# JTAG_MCU.net
KiCad netlist of a schematic drawn in Altium Designer
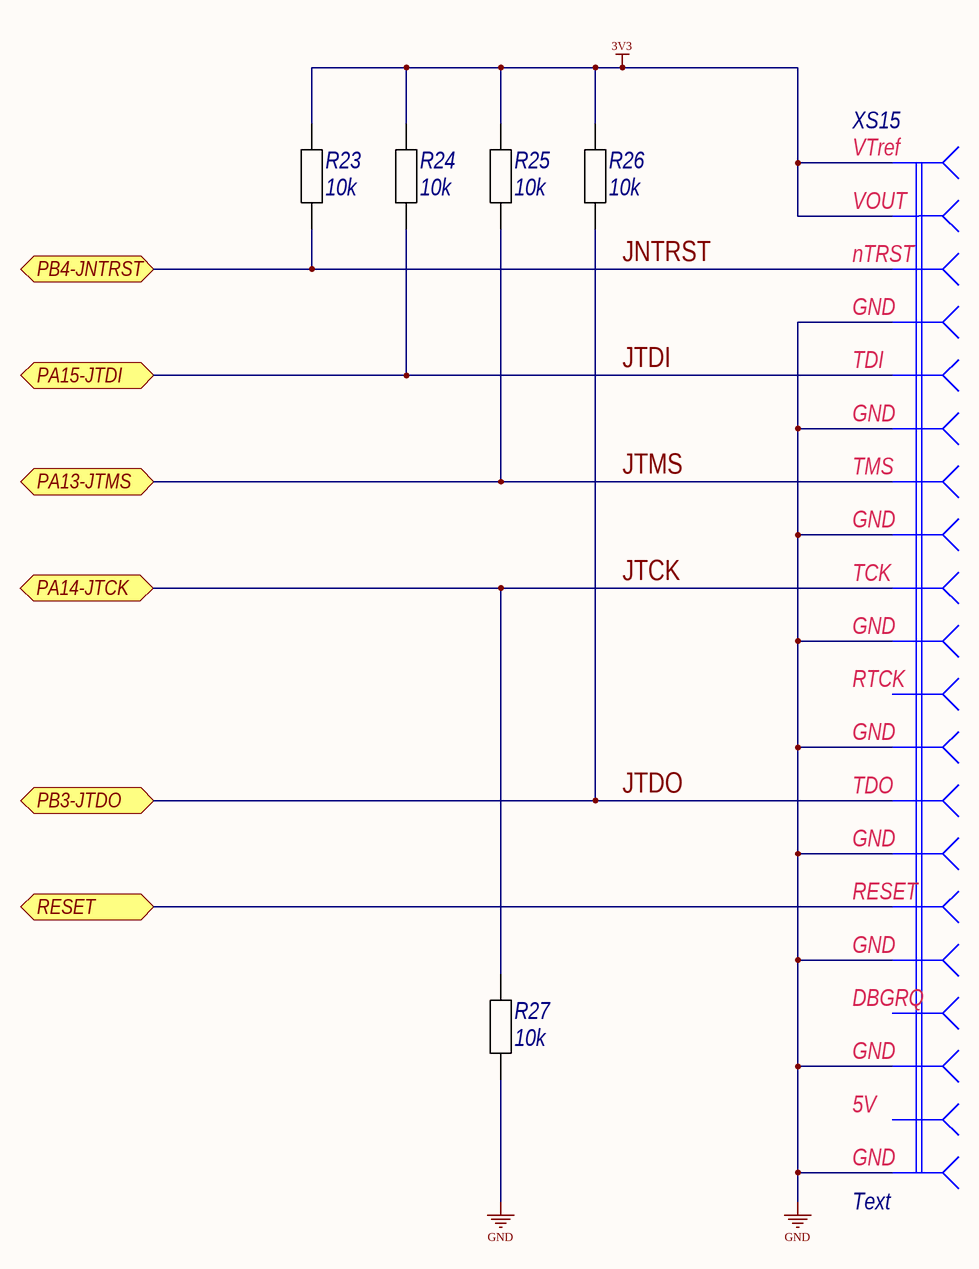
[diagram p0: JTAG_MCU.SchDoc]

(export (version "E")
  (design (tool "Eeschema 10.0.6"))
  (components
    (comp (ref "R23")
      (value "10k")
      (footprint "C0805R")
      (fields (field (name "PUBLISHER") "Andrew Danich"))
      (libsource (lib "PA_control_board") (part "R0805"))
    )
    (comp (ref "R24")
      (value "10k")
      (footprint "C0805R")
      (fields (field (name "PUBLISHER") "Andrew Danich"))
      (libsource (lib "PA_control_board") (part "R0805"))
    )
    (comp (ref "R25")
      (value "10k")
      (footprint "C0805R")
      (fields (field (name "PUBLISHER") "Andrew Danich"))
      (libsource (lib "PA_control_board") (part "R0805"))
    )
    (comp (ref "R26")
      (value "10k")
      (footprint "C0805R")
      (fields (field (name "PUBLISHER") "Andrew Danich"))
      (libsource (lib "PA_control_board") (part "R0805"))
    )
    (comp (ref "R27")
      (value "10k")
      (footprint "C0805R")
      (fields (field (name "PUBLISHER") "Andrew Danich"))
      (libsource (lib "PA_control_board") (part "R0805"))
    )
    (comp (ref "XS15")
      (value "Text")
      (footprint "IDC-20")
      (fields (field (name "PUBLISHER") "Andrew Danich"))
      (libsource (lib "PA_control_board") (part "JTAG"))
    )
  )
  (nets
    (net (code "2") (name "/JNTRST") (class "Default")
      (node (ref "R23") (pin "1") (pinfunction "1_1") (pintype "passive"))
      (node (ref "XS15") (pin "3") (pintype "passive"))
    )
    (net (code "3") (name "/JTCK") (class "Default")
      (node (ref "R27") (pin "2") (pinfunction "2_2") (pintype "passive"))
      (node (ref "XS15") (pin "9") (pintype "passive"))
    )
    (net (code "4") (name "/JTDI") (class "Default")
      (node (ref "R24") (pin "1") (pinfunction "1_1") (pintype "passive"))
      (node (ref "XS15") (pin "5") (pintype "passive"))
    )
    (net (code "5") (name "/JTDO") (class "Default")
      (node (ref "R26") (pin "1") (pinfunction "1_1") (pintype "passive"))
      (node (ref "XS15") (pin "13") (pintype "passive"))
    )
    (net (code "6") (name "/JTMS") (class "Default")
      (node (ref "R25") (pin "1") (pinfunction "1_1") (pintype "passive"))
      (node (ref "XS15") (pin "7") (pintype "passive"))
    )
    (net (code "7") (name "/RESET") (class "Default") (node (ref "XS15") (pin "15") (pintype "passive")))
    (net (code "8") (name "3V3") (class "Default")
      (node (ref "R23") (pin "2") (pinfunction "2_2") (pintype "passive"))
      (node (ref "R24") (pin "2") (pinfunction "2_2") (pintype "passive"))
      (node (ref "R25") (pin "2") (pinfunction "2_2") (pintype "passive"))
      (node (ref "R26") (pin "2") (pinfunction "2_2") (pintype "passive"))
      (node (ref "XS15") (pin "1") (pintype "passive"))
      (node (ref "XS15") (pin "2") (pintype "passive"))
    )
    (net (code "9") (name "GND") (class "Default")
      (node (ref "R27") (pin "1") (pinfunction "1_1") (pintype "passive"))
      (node (ref "XS15") (pin "10") (pintype "passive"))
      (node (ref "XS15") (pin "12") (pintype "passive"))
      (node (ref "XS15") (pin "14") (pintype "passive"))
      (node (ref "XS15") (pin "16") (pintype "passive"))
      (node (ref "XS15") (pin "18") (pintype "passive"))
      (node (ref "XS15") (pin "20") (pintype "passive"))
      (node (ref "XS15") (pin "4") (pintype "passive"))
      (node (ref "XS15") (pin "6") (pintype "passive"))
      (node (ref "XS15") (pin "8") (pintype "passive"))
    )
    (net (code "10") (name "unconnected-(XS15-Pad11)") (class "Default")
      (node (ref "XS15") (pin "11") (pintype "passive"))
    )
    (net (code "11") (name "unconnected-(XS15-Pad17)") (class "Default")
      (node (ref "XS15") (pin "17") (pintype "passive"))
    )
    (net (code "12") (name "unconnected-(XS15-Pad19)") (class "Default")
      (node (ref "XS15") (pin "19") (pintype "passive"))
    )
  )
)
